# lm3405-12v.net
KiCad netlist of a schematic drawn in EAGLE
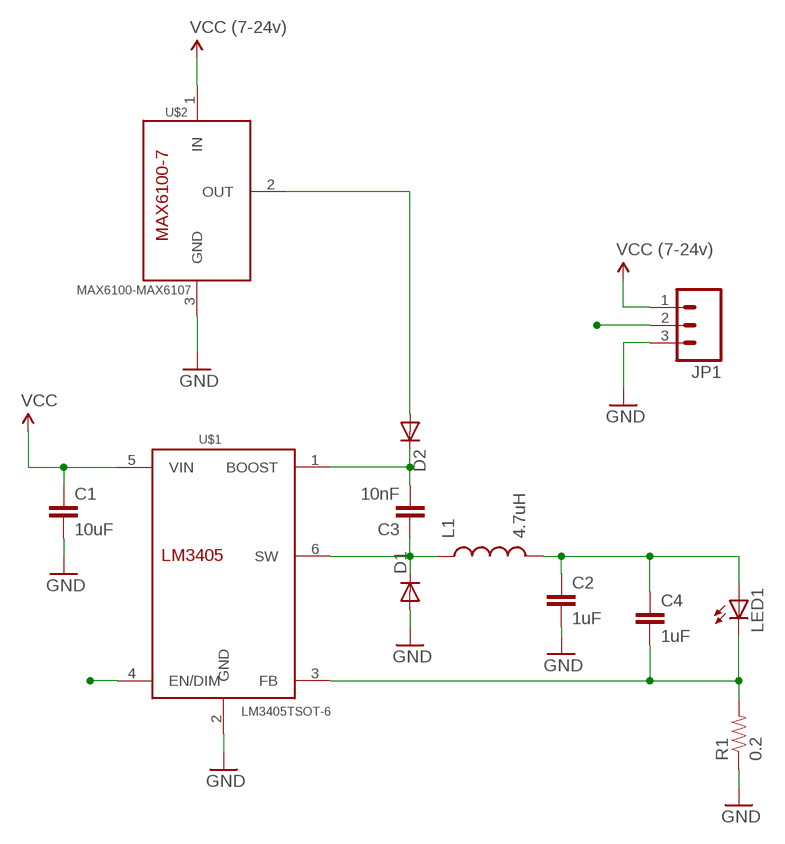
[diagram p0: schematic, sheet 1]

(export (version "E")
  (design (tool "Eeschema 10.0.6"))
  (components
    (comp (ref "C1")
      (value "10uF")
      (footprint "eagle-import:0805")
      (libsource (lib "eagle-import") (part "CAP0805"))
    )
    (comp (ref "C2")
      (value "1uF")
      (footprint "eagle-import:1206")
      (libsource (lib "eagle-import") (part "CAP1206"))
    )
    (comp (ref "C3")
      (value "10nF")
      (footprint "eagle-import:0805")
      (libsource (lib "eagle-import") (part "CAP0805"))
    )
    (comp (ref "C4")
      (value "1uF")
      (footprint "eagle-import:1206")
      (libsource (lib "eagle-import") (part "CAP1206"))
    )
    (comp (ref "D1")
      (value "DIODESMA")
      (footprint "eagle-import:SMA-DIODE")
      (libsource (lib "eagle-import") (part "DIODESMA"))
    )
    (comp (ref "D2")
      (value "DIODESOD")
      (footprint "eagle-import:SOD-323")
      (libsource (lib "eagle-import") (part "DIODESOD"))
    )
    (comp (ref "JP1")
      (value "M03PTH")
      (footprint "eagle-import:1X03")
      (libsource (lib "eagle-import") (part "M03PTH"))
    )
    (comp (ref "L1")
      (value "4.7uH")
      (footprint "eagle-import:1210")
      (libsource (lib "eagle-import") (part "INDUCTOR1210"))
    )
    (comp (ref "LED1")
      (value "LED3MM")
      (footprint "eagle-import:LED3MM")
      (libsource (lib "eagle-import") (part "LED3MM"))
    )
    (comp (ref "R1")
      (value "0.2")
      (footprint "eagle-import:R2010")
      (libsource (lib "eagle-import") (part "RESISTOR2010"))
    )
    (comp (ref "U$1")
      (value "LM3405TSOT-6")
      (footprint "eagle-import:TSOT-6")
      (libsource (lib "eagle-import") (part "LM3405TSOT-6"))
    )
    (comp (ref "U$2")
      (value "MAX6100-MAX6107")
      (footprint "eagle-import:SOT-23-3")
      (libsource (lib "eagle-import") (part "MAX6100-MAX6107"))
    )
  )
  (nets
    (net (code "1") (name "/PWM") (class "Default")
      (node (ref "JP1") (pin "2") (pinfunction "2_2") (pintype "passive"))
      (node (ref "U$1") (pin "4") (pinfunction "EN/DIM_4") (pintype "bidirectional"))
    )
    (net (code "2") (name "GND") (class "Default")
      (node (ref "C1") (pin "2") (pinfunction "2_2") (pintype "passive"))
      (node (ref "C2") (pin "2") (pinfunction "2_2") (pintype "passive"))
      (node (ref "D1") (pin "A") (pinfunction "A_A") (pintype "passive"))
      (node (ref "JP1") (pin "3") (pinfunction "3_3") (pintype "passive"))
      (node (ref "R1") (pin "1") (pinfunction "1_1") (pintype "passive"))
      (node (ref "U$1") (pin "2") (pinfunction "GND_2") (pintype "bidirectional"))
      (node (ref "U$2") (pin "3") (pinfunction "GND_3") (pintype "bidirectional"))
    )
    (net (code "3") (name "Net-(C2-Pad1)") (class "Default")
      (node (ref "C2") (pin "1") (pinfunction "1_1") (pintype "passive"))
      (node (ref "C4") (pin "1") (pinfunction "1_1") (pintype "passive"))
      (node (ref "L1") (pin "2") (pinfunction "2_2") (pintype "passive"))
      (node (ref "LED1") (pin "A") (pinfunction "A_A") (pintype "passive"))
    )
    (net (code "4") (name "Net-(D2-A)") (class "Default")
      (node (ref "D2") (pin "2") (pinfunction "A_2") (pintype "passive"))
      (node (ref "U$2") (pin "2") (pinfunction "OUT_2") (pintype "bidirectional"))
    )
    (net (code "5") (name "Net-(D2-C)") (class "Default")
      (node (ref "C3") (pin "2") (pinfunction "2_2") (pintype "passive"))
      (node (ref "D2") (pin "1") (pinfunction "C_1") (pintype "passive"))
      (node (ref "U$1") (pin "1") (pinfunction "BOOST_1") (pintype "bidirectional"))
    )
    (net (code "6") (name "Net-(LED1-C)") (class "Default")
      (node (ref "C4") (pin "2") (pinfunction "2_2") (pintype "passive"))
      (node (ref "LED1") (pin "K") (pinfunction "C_K") (pintype "passive"))
      (node (ref "R1") (pin "2") (pinfunction "2_2") (pintype "passive"))
      (node (ref "U$1") (pin "3") (pinfunction "FB_3") (pintype "bidirectional"))
    )
    (net (code "7") (name "Net-(U$1-SW)") (class "Default")
      (node (ref "C3") (pin "1") (pinfunction "1_1") (pintype "passive"))
      (node (ref "D1") (pin "C") (pinfunction "C_C") (pintype "passive"))
      (node (ref "L1") (pin "1") (pinfunction "1_1") (pintype "passive"))
      (node (ref "U$1") (pin "6") (pinfunction "SW_6") (pintype "bidirectional"))
    )
    (net (code "8") (name "VCC") (class "Default")
      (node (ref "C1") (pin "1") (pinfunction "1_1") (pintype "passive"))
      (node (ref "JP1") (pin "1") (pinfunction "1_1") (pintype "passive"))
      (node (ref "U$1") (pin "5") (pinfunction "VIN_5") (pintype "bidirectional"))
      (node (ref "U$2") (pin "1") (pinfunction "IN_1") (pintype "bidirectional"))
    )
  )
)
